# esp32-dev-board-v1_1.net
KiCad netlist of a schematic drawn in EasyEDA Pro
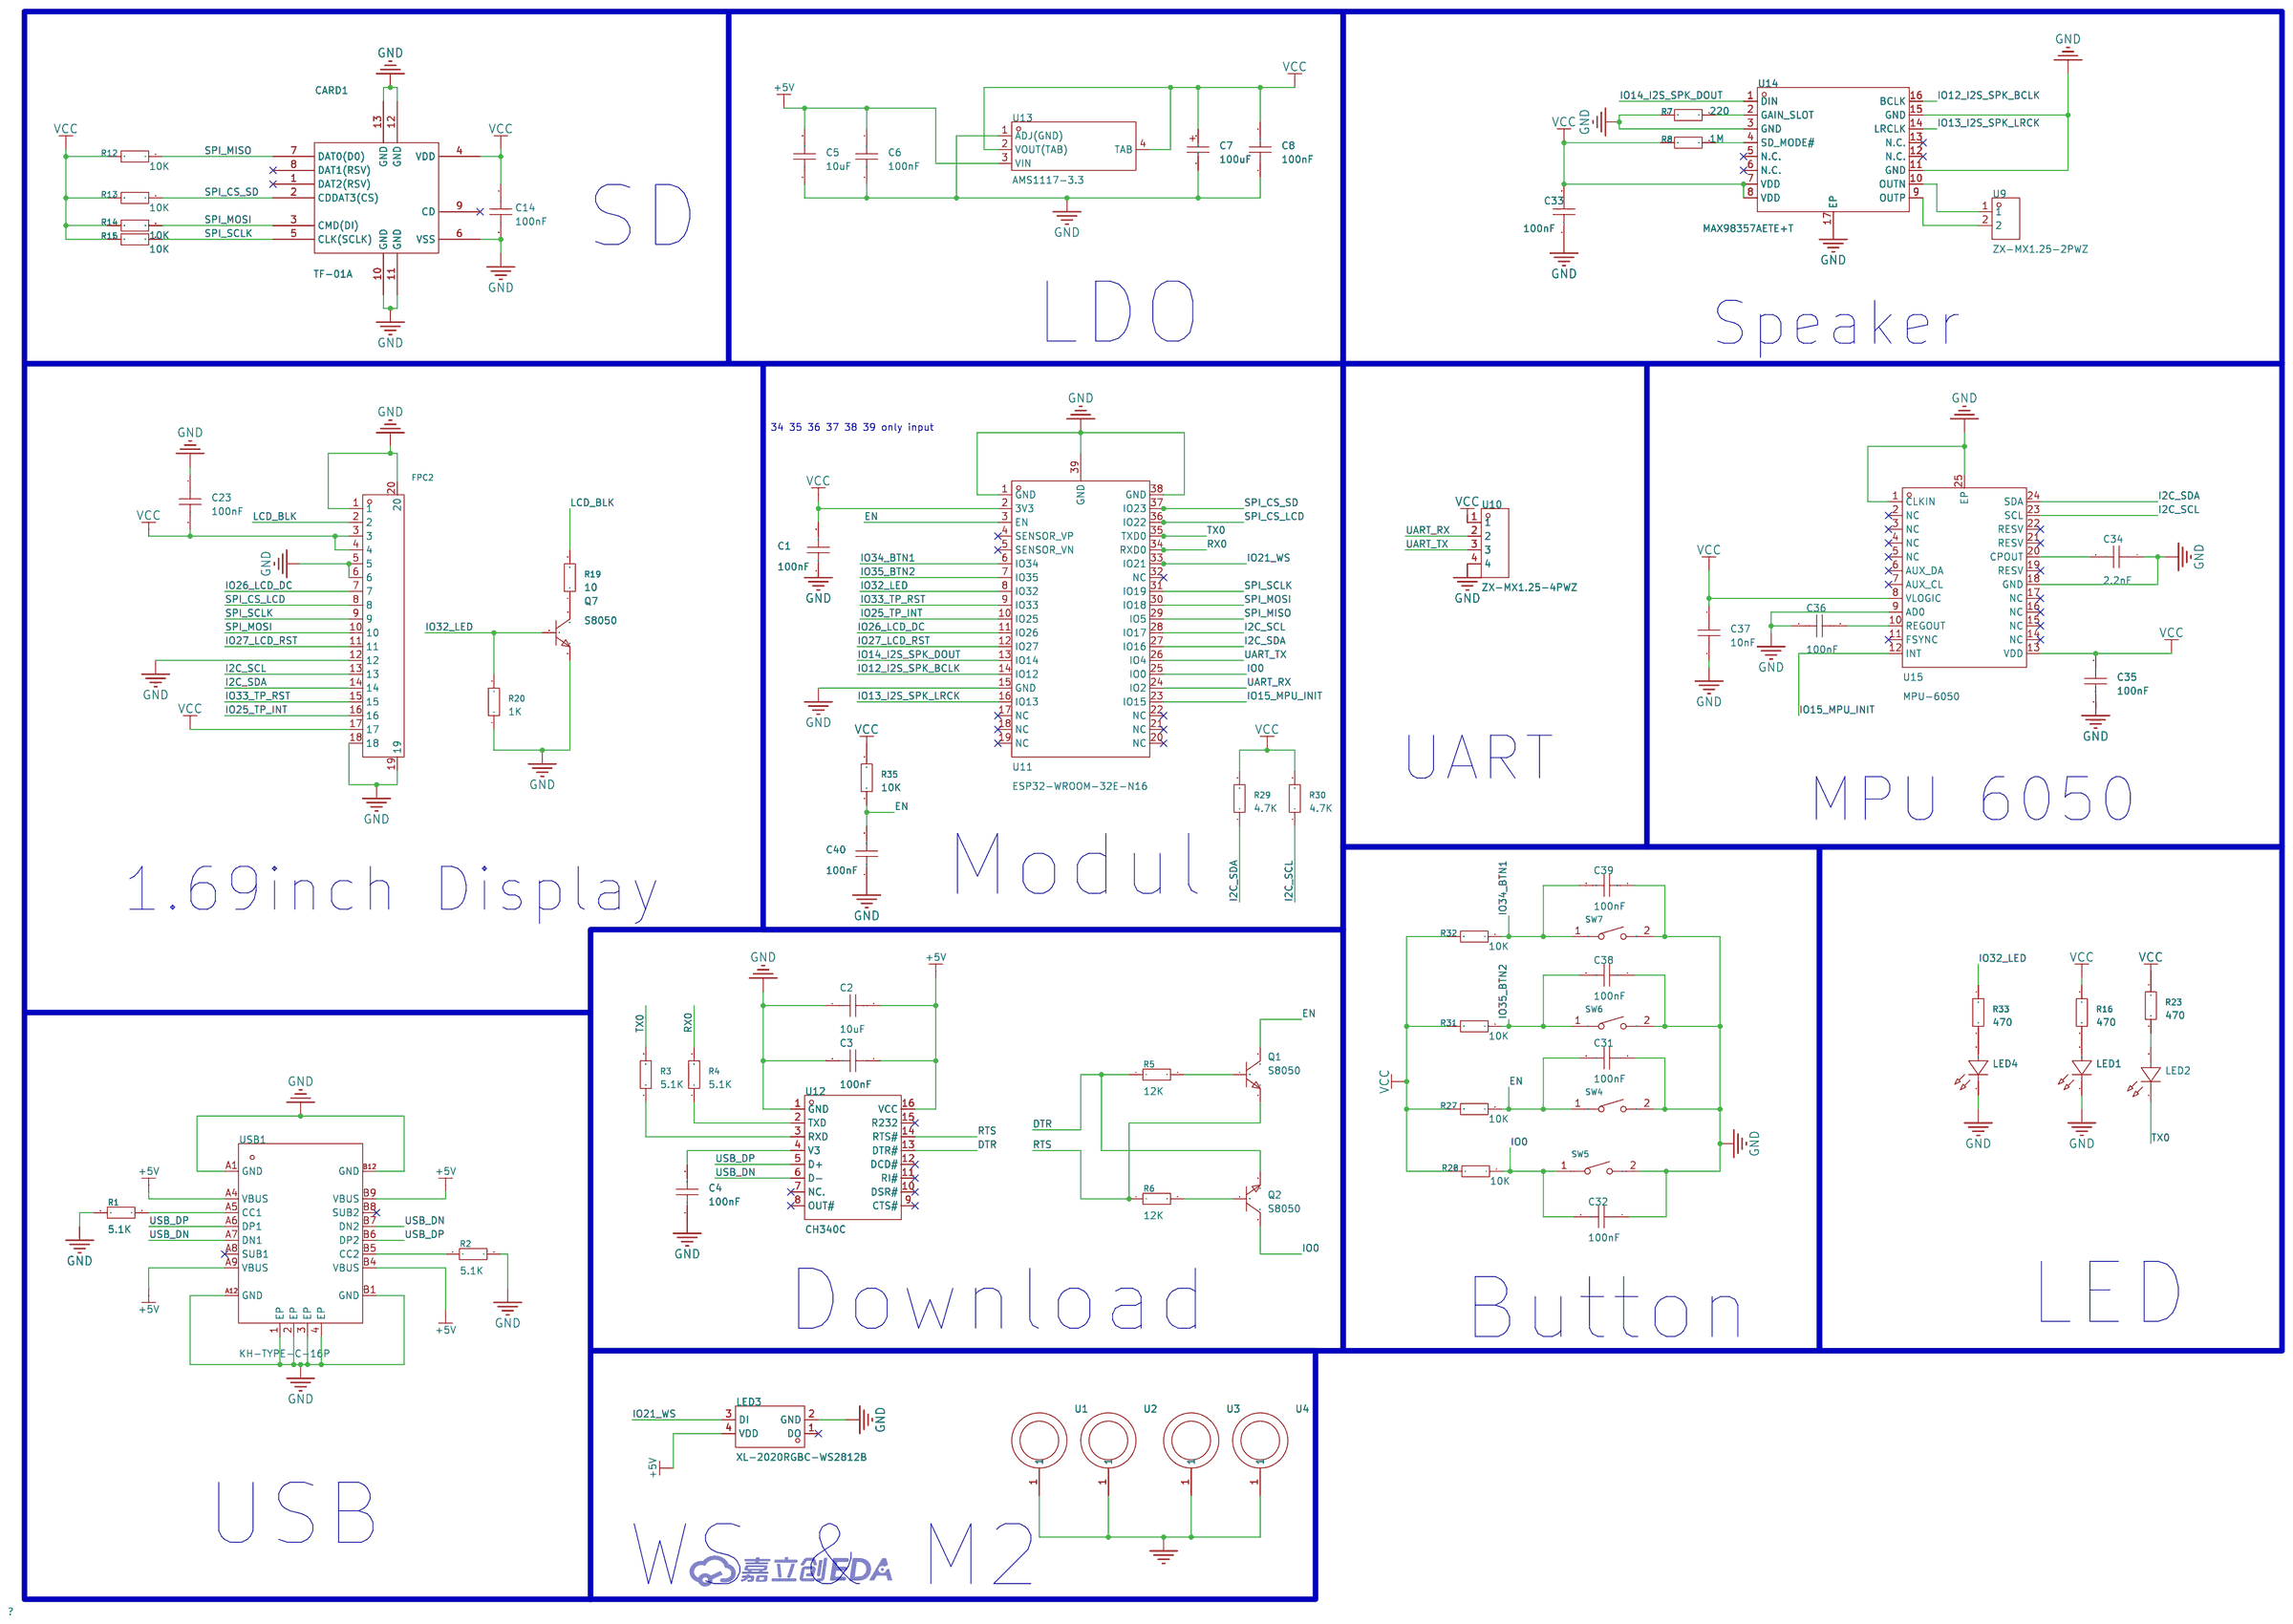
[diagram p0: schematic sheet]

(export (version "E")
  (design (tool "Eeschema 10.0.6"))
  (components
    (comp (ref "C1")
      (value "100nF")
      (footprint "easyedapro:C0402")
      (fields
        (field (name "Manufacturer Part") "CL05B104KO5NNNC")
        (field (name "Manufacturer") "SAMSUNG(三星)")
      )
      (libsource (lib "easyedapro") (part "CL05B104KO5NNNC"))
    )
    (comp (ref "C2")
      (value "10uF")
      (footprint "easyedapro:C0603")
      (fields
        (field (name "Manufacturer Part") "CGA0603X5R106K100JT")
        (field (name "Manufacturer") "HRE(芯声)")
      )
      (libsource (lib "easyedapro") (part "CGA0603X5R106K100JT"))
    )
    (comp (ref "C3")
      (value "100nF")
      (footprint "easyedapro:C0402")
      (fields
        (field (name "Manufacturer Part") "CL05B104KO5NNNC")
        (field (name "Manufacturer") "SAMSUNG(三星)")
      )
      (libsource (lib "easyedapro") (part "CL05B104KO5NNNC"))
    )
    (comp (ref "C4")
      (value "100nF")
      (footprint "easyedapro:C0402")
      (fields
        (field (name "Manufacturer Part") "CL05B104KO5NNNC")
        (field (name "Manufacturer") "SAMSUNG(三星)")
      )
      (libsource (lib "easyedapro") (part "CL05B104KO5NNNC"))
    )
    (comp (ref "C5")
      (value "10uF")
      (footprint "easyedapro:C0603")
      (fields
        (field (name "Manufacturer Part") "CGA0603X5R106K100JT")
        (field (name "Manufacturer") "HRE(芯声)")
      )
      (libsource (lib "easyedapro") (part "CGA0603X5R106K100JT"))
    )
    (comp (ref "C6")
      (value "100nF")
      (footprint "easyedapro:C0402")
      (fields
        (field (name "Manufacturer Part") "CL05B104KO5NNNC")
        (field (name "Manufacturer") "SAMSUNG(三星)")
      )
      (libsource (lib "easyedapro") (part "CL05B104KO5NNNC"))
    )
    (comp (ref "C7")
      (value "100uF")
      (footprint "easyedapro:CASE-B_3528")
      (fields (field (name "Manufacturer Part") "TAJB107K006RNJ") (field (name "Manufacturer") "Kyocera AVX"))
      (libsource (lib "easyedapro") (part "TAJB107K006RNJ"))
    )
    (comp (ref "C8")
      (value "100nF")
      (footprint "easyedapro:C0402")
      (fields
        (field (name "Manufacturer Part") "CL05B104KO5NNNC")
        (field (name "Manufacturer") "SAMSUNG(三星)")
      )
      (libsource (lib "easyedapro") (part "CL05B104KO5NNNC"))
    )
    (comp (ref "C14")
      (value "100nF")
      (footprint "easyedapro:C0402")
      (fields
        (field (name "Manufacturer Part") "CL05B104KO5NNNC")
        (field (name "Manufacturer") "SAMSUNG(三星)")
      )
      (libsource (lib "easyedapro") (part "CL05B104KO5NNNC"))
    )
    (comp (ref "C23")
      (value "100nF")
      (footprint "easyedapro:C0402")
      (fields
        (field (name "Manufacturer Part") "CL05B104KO5NNNC")
        (field (name "Manufacturer") "SAMSUNG(三星)")
      )
      (libsource (lib "easyedapro") (part "CL05B104KO5NNNC"))
    )
    (comp (ref "C31")
      (value "100nF")
      (footprint "easyedapro:C0402")
      (fields
        (field (name "Manufacturer Part") "CL05B104KO5NNNC")
        (field (name "Manufacturer") "SAMSUNG(三星)")
      )
      (libsource (lib "easyedapro") (part "CL05B104KO5NNNC"))
    )
    (comp (ref "C32")
      (value "100nF")
      (footprint "easyedapro:C0402")
      (fields
        (field (name "Manufacturer Part") "CL05B104KO5NNNC")
        (field (name "Manufacturer") "SAMSUNG(三星)")
      )
      (libsource (lib "easyedapro") (part "CL05B104KO5NNNC"))
    )
    (comp (ref "C33")
      (value "100nF")
      (footprint "easyedapro:C0402")
      (fields
        (field (name "Manufacturer Part") "CL05B104KO5NNNC")
        (field (name "Manufacturer") "SAMSUNG(三星)")
      )
      (libsource (lib "easyedapro") (part "CL05B104KO5NNNC"))
    )
    (comp (ref "C34")
      (value "2.2nF")
      (footprint "easyedapro:C0402")
      (fields
        (field (name "Manufacturer Part") "CL05B104KO5NNNC")
        (field (name "Manufacturer") "SAMSUNG(三星)")
      )
      (libsource (lib "easyedapro") (part "CL05B104KO5NNNC"))
    )
    (comp (ref "C35")
      (value "100nF")
      (footprint "easyedapro:C0402")
      (fields
        (field (name "Manufacturer Part") "CL05B104KO5NNNC")
        (field (name "Manufacturer") "SAMSUNG(三星)")
      )
      (libsource (lib "easyedapro") (part "CL05B104KO5NNNC"))
    )
    (comp (ref "C36")
      (value "100nF")
      (footprint "easyedapro:C0402")
      (fields
        (field (name "Manufacturer Part") "CL05B104KO5NNNC")
        (field (name "Manufacturer") "SAMSUNG(三星)")
      )
      (libsource (lib "easyedapro") (part "CL05B104KO5NNNC"))
    )
    (comp (ref "C37")
      (value "10nF")
      (footprint "easyedapro:C0402")
      (fields
        (field (name "Manufacturer Part") "CL05B104KO5NNNC")
        (field (name "Manufacturer") "SAMSUNG(三星)")
      )
      (libsource (lib "easyedapro") (part "CL05B104KO5NNNC"))
    )
    (comp (ref "C38")
      (value "100nF")
      (footprint "easyedapro:C0402")
      (fields
        (field (name "Manufacturer Part") "CL05B104KO5NNNC")
        (field (name "Manufacturer") "SAMSUNG(三星)")
      )
      (libsource (lib "easyedapro") (part "CL05B104KO5NNNC"))
    )
    (comp (ref "C39")
      (value "100nF")
      (footprint "easyedapro:C0402")
      (fields
        (field (name "Manufacturer Part") "CL05B104KO5NNNC")
        (field (name "Manufacturer") "SAMSUNG(三星)")
      )
      (libsource (lib "easyedapro") (part "CL05B104KO5NNNC"))
    )
    (comp (ref "C40")
      (value "100nF")
      (footprint "easyedapro:C0402")
      (fields
        (field (name "Manufacturer Part") "CL05B104KO5NNNC")
        (field (name "Manufacturer") "SAMSUNG(三星)")
      )
      (libsource (lib "easyedapro") (part "CL05B104KO5NNNC"))
    )
    (comp (ref "CARD1")
      (value "TF-01A")
      (footprint "easyedapro:TF-SMD_TF-01A")
      (fields (field (name "Manufacturer") "韩国韩荣"))
      (libsource (lib "easyedapro") (part "TF-01A"))
    )
    (comp (ref "FPC2")
      (value "FPC-05F-18PH20")
      (footprint "easyedapro:FPC-SMD_18P-P0.50_FPC-05F-18PH20")
      (fields (field (name "Manufacturer") "XUNPU(讯普)"))
      (libsource (lib "easyedapro") (part "FPC-05F-18PH20"))
    )
    (comp (ref "LED1")
      (value "XL-1608SURC-06")
      (footprint "easyedapro:LED0603-RD_RED")
      (fields (field (name "Manufacturer") "XINGLIGHT(成兴光)"))
      (libsource (lib "easyedapro") (part "XL-1608SURC-06"))
    )
    (comp (ref "LED2")
      (value "XL-1608SURC-06")
      (footprint "easyedapro:LED0603-RD_RED")
      (fields (field (name "Manufacturer") "XINGLIGHT(成兴光)"))
      (libsource (lib "easyedapro") (part "XL-1608SURC-06"))
    )
    (comp (ref "LED3")
      (value "XL-2020RGBC-WS2812B")
      (footprint "easyedapro:LED-SMD_4P-L2.0-W2.0-BR-1")
      (fields (field (name "Manufacturer") "XINGLIGHT(成兴光)"))
      (libsource (lib "easyedapro") (part "XL-2020RGBC-WS2812B"))
    )
    (comp (ref "LED4")
      (value "XL-1608SURC-06")
      (footprint "easyedapro:LED0603-RD_RED")
      (fields (field (name "Manufacturer") "XINGLIGHT(成兴光)"))
      (libsource (lib "easyedapro") (part "XL-1608SURC-06"))
    )
    (comp (ref "Q1")
      (value "S8050")
      (footprint "easyedapro:SOT-23-3_L2.9-W1.3-P1.90-LS2.3-BR")
      (fields (field (name "Manufacturer") "宏迦橙"))
      (libsource (lib "easyedapro") (part "S8050_C20069125"))
    )
    (comp (ref "Q2")
      (value "S8050")
      (footprint "easyedapro:SOT-23-3_L2.9-W1.3-P1.90-LS2.3-BR")
      (fields (field (name "Manufacturer") "宏迦橙"))
      (libsource (lib "easyedapro") (part "S8050_C20069125"))
    )
    (comp (ref "Q7")
      (value "S8050")
      (fields (field (name "Manufacturer") "宏迦橙"))
      (libsource (lib "easyedapro") (part "S8050_C20069125"))
    )
    (comp (ref "R1")
      (value "5.1K")
      (footprint "easyedapro:R0402")
      (fields
        (field (name "Manufacturer Part") "0402WGF4700TCE")
        (field (name "Manufacturer") "UNI-ROYAL(厚声)")
      )
      (libsource (lib "easyedapro") (part "0402WGF4700TCE"))
    )
    (comp (ref "R2")
      (value "5.1K")
      (footprint "easyedapro:R0402")
      (fields
        (field (name "Manufacturer Part") "0402WGF4700TCE")
        (field (name "Manufacturer") "UNI-ROYAL(厚声)")
      )
      (libsource (lib "easyedapro") (part "0402WGF4700TCE"))
    )
    (comp (ref "R3")
      (value "5.1K")
      (footprint "easyedapro:R0402")
      (fields
        (field (name "Manufacturer Part") "0402WGF4700TCE")
        (field (name "Manufacturer") "UNI-ROYAL(厚声)")
      )
      (libsource (lib "easyedapro") (part "0402WGF4700TCE"))
    )
    (comp (ref "R4")
      (value "5.1K")
      (footprint "easyedapro:R0402")
      (fields
        (field (name "Manufacturer Part") "0402WGF4700TCE")
        (field (name "Manufacturer") "UNI-ROYAL(厚声)")
      )
      (libsource (lib "easyedapro") (part "0402WGF4700TCE"))
    )
    (comp (ref "R5")
      (value "12K")
      (footprint "easyedapro:R0402")
      (fields
        (field (name "Manufacturer Part") "0402WGF4700TCE")
        (field (name "Manufacturer") "UNI-ROYAL(厚声)")
      )
      (libsource (lib "easyedapro") (part "0402WGF4700TCE"))
    )
    (comp (ref "R6")
      (value "12K")
      (footprint "easyedapro:R0402")
      (fields
        (field (name "Manufacturer Part") "0402WGF4700TCE")
        (field (name "Manufacturer") "UNI-ROYAL(厚声)")
      )
      (libsource (lib "easyedapro") (part "0402WGF4700TCE"))
    )
    (comp (ref "R7")
      (value "220")
      (footprint "easyedapro:R0402")
      (fields
        (field (name "Manufacturer Part") "0402WGF4700TCE")
        (field (name "Manufacturer") "UNI-ROYAL(厚声)")
      )
      (libsource (lib "easyedapro") (part "0402WGF4700TCE"))
    )
    (comp (ref "R8")
      (value "1M")
      (footprint "easyedapro:R0402")
      (fields
        (field (name "Manufacturer Part") "0402WGF4700TCE")
        (field (name "Manufacturer") "UNI-ROYAL(厚声)")
      )
      (libsource (lib "easyedapro") (part "0402WGF4700TCE"))
    )
    (comp (ref "R12")
      (value "10K")
      (footprint "easyedapro:R0402")
      (fields
        (field (name "Manufacturer Part") "0402WGF4700TCE")
        (field (name "Manufacturer") "UNI-ROYAL(厚声)")
      )
      (libsource (lib "easyedapro") (part "0402WGF4700TCE"))
    )
    (comp (ref "R13")
      (value "10K")
      (footprint "easyedapro:R0402")
      (fields
        (field (name "Manufacturer Part") "0402WGF4700TCE")
        (field (name "Manufacturer") "UNI-ROYAL(厚声)")
      )
      (libsource (lib "easyedapro") (part "0402WGF4700TCE"))
    )
    (comp (ref "R14")
      (value "10K")
      (footprint "easyedapro:R0402")
      (fields
        (field (name "Manufacturer Part") "0402WGF4700TCE")
        (field (name "Manufacturer") "UNI-ROYAL(厚声)")
      )
      (libsource (lib "easyedapro") (part "0402WGF4700TCE"))
    )
    (comp (ref "R15")
      (value "10K")
      (footprint "easyedapro:R0402")
      (fields
        (field (name "Manufacturer Part") "0402WGF4700TCE")
        (field (name "Manufacturer") "UNI-ROYAL(厚声)")
      )
      (libsource (lib "easyedapro") (part "0402WGF4700TCE"))
    )
    (comp (ref "R16")
      (value "470")
      (footprint "easyedapro:R0402")
      (fields
        (field (name "Manufacturer Part") "0402WGF4700TCE")
        (field (name "Manufacturer") "UNI-ROYAL(厚声)")
      )
      (libsource (lib "easyedapro") (part "0402WGF4700TCE"))
    )
    (comp (ref "R19")
      (value "10")
      (footprint "easyedapro:R0402")
      (fields
        (field (name "Manufacturer Part") "0402WGF4700TCE")
        (field (name "Manufacturer") "UNI-ROYAL(厚声)")
      )
      (libsource (lib "easyedapro") (part "0402WGF4700TCE"))
    )
    (comp (ref "R20")
      (value "1K")
      (footprint "easyedapro:R0402")
      (fields
        (field (name "Manufacturer Part") "0402WGF4700TCE")
        (field (name "Manufacturer") "UNI-ROYAL(厚声)")
      )
      (libsource (lib "easyedapro") (part "0402WGF4700TCE"))
    )
    (comp (ref "R23")
      (value "470")
      (footprint "easyedapro:R0402")
      (fields
        (field (name "Manufacturer Part") "0402WGF4700TCE")
        (field (name "Manufacturer") "UNI-ROYAL(厚声)")
      )
      (libsource (lib "easyedapro") (part "0402WGF4700TCE"))
    )
    (comp (ref "R27")
      (value "10K")
      (footprint "easyedapro:R0402")
      (fields
        (field (name "Manufacturer Part") "0402WGF4700TCE")
        (field (name "Manufacturer") "UNI-ROYAL(厚声)")
      )
      (libsource (lib "easyedapro") (part "0402WGF4700TCE"))
    )
    (comp (ref "R28")
      (value "10K")
      (footprint "easyedapro:R0402")
      (fields
        (field (name "Manufacturer Part") "0402WGF4700TCE")
        (field (name "Manufacturer") "UNI-ROYAL(厚声)")
      )
      (libsource (lib "easyedapro") (part "0402WGF4700TCE"))
    )
    (comp (ref "R29")
      (value "4.7K")
      (footprint "easyedapro:R0402")
      (fields
        (field (name "Manufacturer Part") "0402WGF4700TCE")
        (field (name "Manufacturer") "UNI-ROYAL(厚声)")
      )
      (libsource (lib "easyedapro") (part "0402WGF4700TCE"))
    )
    (comp (ref "R30")
      (value "4.7K")
      (footprint "easyedapro:R0402")
      (fields
        (field (name "Manufacturer Part") "0402WGF4700TCE")
        (field (name "Manufacturer") "UNI-ROYAL(厚声)")
      )
      (libsource (lib "easyedapro") (part "0402WGF4700TCE"))
    )
    (comp (ref "R31")
      (value "10K")
      (footprint "easyedapro:R0402")
      (fields
        (field (name "Manufacturer Part") "0402WGF4700TCE")
        (field (name "Manufacturer") "UNI-ROYAL(厚声)")
      )
      (libsource (lib "easyedapro") (part "0402WGF4700TCE"))
    )
    (comp (ref "R32")
      (value "10K")
      (footprint "easyedapro:R0402")
      (fields
        (field (name "Manufacturer Part") "0402WGF4700TCE")
        (field (name "Manufacturer") "UNI-ROYAL(厚声)")
      )
      (libsource (lib "easyedapro") (part "0402WGF4700TCE"))
    )
    (comp (ref "R33")
      (value "470")
      (footprint "easyedapro:R0402")
      (fields
        (field (name "Manufacturer Part") "0402WGF4700TCE")
        (field (name "Manufacturer") "UNI-ROYAL(厚声)")
      )
      (libsource (lib "easyedapro") (part "0402WGF4700TCE"))
    )
    (comp (ref "R35")
      (value "10K")
      (footprint "easyedapro:R0402")
      (fields
        (field (name "Manufacturer Part") "0402WGF4700TCE")
        (field (name "Manufacturer") "UNI-ROYAL(厚声)")
      )
      (libsource (lib "easyedapro") (part "0402WGF4700TCE"))
    )
    (comp (ref "SW4")
      (value "TS-1088-AR02016")
      (footprint "easyedapro:SW-SMD_L3.9-W3.0-P4.45")
      (fields (field (name "Manufacturer") "XUNPU(讯普)"))
      (libsource (lib "easyedapro") (part "TS-1088-AR02016"))
    )
    (comp (ref "SW5")
      (value "TS-1088-AR02016")
      (footprint "easyedapro:SW-SMD_L3.9-W3.0-P4.45")
      (fields (field (name "Manufacturer") "XUNPU(讯普)"))
      (libsource (lib "easyedapro") (part "TS-1088-AR02016"))
    )
    (comp (ref "SW6")
      (value "TS-1088-AR02016")
      (footprint "easyedapro:SW-SMD_L3.9-W3.0-P4.45")
      (fields (field (name "Manufacturer") "XUNPU(讯普)"))
      (libsource (lib "easyedapro") (part "TS-1088-AR02016"))
    )
    (comp (ref "SW7")
      (value "TS-1088-AR02016")
      (footprint "easyedapro:SW-SMD_L3.9-W3.0-P4.45")
      (fields (field (name "Manufacturer") "XUNPU(讯普)"))
      (libsource (lib "easyedapro") (part "TS-1088-AR02016"))
    )
    (comp (ref "U1") (value "~") (footprint "easyedapro:M2") (libsource (lib "easyedapro") (part "M2")))
    (comp (ref "U2") (value "~") (footprint "easyedapro:M2") (libsource (lib "easyedapro") (part "M2")))
    (comp (ref "U3") (value "~") (footprint "easyedapro:M2") (libsource (lib "easyedapro") (part "M2")))
    (comp (ref "U4") (value "~") (footprint "easyedapro:M2") (libsource (lib "easyedapro") (part "M2")))
    (comp (ref "U9")
      (value "ZX-MX1.25-2PWZ")
      (footprint "easyedapro:CONN-TH_2P-P1.25_ZX-MX1.25-2PWZ")
      (fields (field (name "Manufacturer") "Megastar(兆星)"))
      (libsource (lib "easyedapro") (part "ZX-MX1.25-2PWZ"))
    )
    (comp (ref "U10")
      (value "ZX-MX1.25-4PWZ")
      (footprint "easyedapro:CONN-TH_4P-P1.25_ZX-MX1.25-4PWZ")
      (fields (field (name "Manufacturer") "Megastar(兆星)"))
      (libsource (lib "easyedapro") (part "ZX-MX1.25-4PWZ"))
    )
    (comp (ref "U11")
      (value "ESP32-WROOM-32E-N16")
      (footprint "easyedapro:WIFI-SMD_ESP32-WROOM-32E")
      (fields (field (name "Manufacturer") "ESPRESSIF(乐鑫)"))
      (libsource (lib "easyedapro") (part "ESP32-WROOM-32E(16MB)"))
    )
    (comp (ref "U12")
      (value "CH340C")
      (footprint "easyedapro:SOP-16_L10.0-W3.9-P1.27-LS6.0-BL")
      (fields (field (name "Manufacturer") "WCH(南京沁恒)"))
      (libsource (lib "easyedapro") (part "CH340C"))
    )
    (comp (ref "U13")
      (value "AMS1117-3.3")
      (footprint "easyedapro:SOT-223-4_L6.5-W3.5-P2.30-LS7.0-BR")
      (fields (field (name "Manufacturer") "UMW(友台半导体)"))
      (libsource (lib "easyedapro") (part "AMS1117-3.3_C347222"))
    )
    (comp (ref "U14")
      (value "MAX98357AETE+T")
      (footprint "easyedapro:TQFN-16_L3.0-W3.0-P0.50-BL-EP1.5")
      (fields (field (name "Manufacturer") "ADI(亚德诺)/MAXIM(美信)"))
      (libsource (lib "easyedapro") (part "MAX98357AETE+T"))
    )
    (comp (ref "U15")
      (value "MPU-6050")
      (footprint "easyedapro:QFN-24_L4.0-W4.0-P0.50-BL-EP2.7")
      (description "Sensor Type:加速度计陀螺仪 Operating Temperature:-40°C~+85°C Operating Temperature:-40°C~+85°C")
      (fields (field (name "Manufacturer") "TDK InvenSense(应美盛)"))
      (libsource (lib "easyedapro") (part "MPU-6050_C24112"))
    )
    (comp (ref "USB1")
      (value "KH-TYPE-C-16P")
      (footprint "easyedapro:USB-C-SMD_KH-TYPE-C-16P")
      (fields (field (name "Manufacturer") "kinghelm(金航标)"))
      (libsource (lib "easyedapro") (part "KH-TYPE-C-16P"))
    )
  )
  (nets
    (net (code "1") (name "+5V") (class "Default")
      (node (ref "C2") (pin "2") (pinfunction "2_2") (pintype "unspecified"))
      (node (ref "C3") (pin "1") (pinfunction "1_1") (pintype "unspecified"))
      (node (ref "C5") (pin "2") (pinfunction "2_2") (pintype "unspecified"))
      (node (ref "C6") (pin "1") (pinfunction "1_1") (pintype "unspecified"))
      (node (ref "LED3") (pin "4") (pinfunction "VDD_4") (pintype "unspecified"))
      (node (ref "U12") (pin "16") (pinfunction "VCC_16") (pintype "unspecified"))
      (node (ref "U13") (pin "3") (pinfunction "VIN_3") (pintype "unspecified"))
      (node (ref "USB1") (pin "A4") (pinfunction "VBUS_A4") (pintype "unspecified"))
      (node (ref "USB1") (pin "A9") (pinfunction "VBUS_A9") (pintype "unspecified"))
      (node (ref "USB1") (pin "B4") (pinfunction "VBUS_B4") (pintype "unspecified"))
      (node (ref "USB1") (pin "B9") (pinfunction "VBUS_B9") (pintype "unspecified"))
    )
    (net (code "2") (name "/DTR") (class "Default")
      (node (ref "Q2") (pin "2") (pinfunction "E_2") (pintype "input"))
      (node (ref "R5") (pin "1") (pinfunction "1_1") (pintype "input"))
      (node (ref "U12") (pin "13") (pinfunction "DTR#_13") (pintype "unspecified"))
    )
    (net (code "3") (name "/EN") (class "Default")
      (node (ref "C31") (pin "2") (pinfunction "2_2") (pintype "unspecified"))
      (node (ref "C40") (pin "2") (pinfunction "2_2") (pintype "unspecified"))
      (node (ref "Q1") (pin "3") (pinfunction "C_3") (pintype "input"))
      (node (ref "R27") (pin "1") (pinfunction "1_1") (pintype "input"))
      (node (ref "R35") (pin "1") (pinfunction "1_1") (pintype "input"))
      (node (ref "SW4") (pin "1") (pinfunction "1_1") (pintype "input"))
      (node (ref "U11") (pin "3") (pinfunction "EN_3") (pintype "unspecified"))
    )
    (net (code "4") (name "/I2C_SCL") (class "Default")
      (node (ref "FPC2") (pin "13") (pinfunction "13_13") (pintype "input"))
      (node (ref "R30") (pin "1") (pinfunction "1_1") (pintype "input"))
      (node (ref "U11") (pin "28") (pinfunction "IO17_28") (pintype "unspecified"))
      (node (ref "U15") (pin "23") (pinfunction "SCL_23") (pintype "unspecified"))
    )
    (net (code "5") (name "/I2C_SDA") (class "Default")
      (node (ref "FPC2") (pin "14") (pinfunction "14_14") (pintype "input"))
      (node (ref "R29") (pin "1") (pinfunction "1_1") (pintype "input"))
      (node (ref "U11") (pin "27") (pinfunction "IO16_27") (pintype "unspecified"))
      (node (ref "U15") (pin "24") (pinfunction "SDA_24") (pintype "unspecified"))
    )
    (net (code "6") (name "/IO0") (class "Default")
      (node (ref "C32") (pin "2") (pinfunction "2_2") (pintype "unspecified"))
      (node (ref "Q2") (pin "3") (pinfunction "C_3") (pintype "input"))
      (node (ref "R28") (pin "1") (pinfunction "1_1") (pintype "input"))
      (node (ref "SW5") (pin "1") (pinfunction "1_1") (pintype "input"))
      (node (ref "U11") (pin "25") (pinfunction "IO0_25") (pintype "unspecified"))
    )
    (net (code "7") (name "/IO12_I2S_SPK_BCLK") (class "Default")
      (node (ref "U11") (pin "14") (pinfunction "IO12_14") (pintype "unspecified"))
      (node (ref "U14") (pin "16") (pinfunction "BCLK_16") (pintype "unspecified"))
    )
    (net (code "8") (name "/IO13_I2S_SPK_LRCK") (class "Default")
      (node (ref "U11") (pin "16") (pinfunction "IO13_16") (pintype "unspecified"))
      (node (ref "U14") (pin "14") (pinfunction "LRCLK_14") (pintype "unspecified"))
    )
    (net (code "9") (name "/IO14_I2S_SPK_DOUT") (class "Default")
      (node (ref "U11") (pin "13") (pinfunction "IO14_13") (pintype "unspecified"))
      (node (ref "U14") (pin "1") (pinfunction "DIN_1") (pintype "unspecified"))
    )
    (net (code "10") (name "/IO15_MPU_INIT") (class "Default")
      (node (ref "U11") (pin "23") (pinfunction "IO15_23") (pintype "unspecified"))
      (node (ref "U15") (pin "12") (pinfunction "INT_12") (pintype "unspecified"))
    )
    (net (code "11") (name "/IO21_WS") (class "Default")
      (node (ref "LED3") (pin "3") (pinfunction "DI_3") (pintype "unspecified"))
      (node (ref "U11") (pin "33") (pinfunction "IO21_33") (pintype "unspecified"))
    )
    (net (code "12") (name "/IO25_TP_INT") (class "Default")
      (node (ref "FPC2") (pin "16") (pinfunction "16_16") (pintype "input"))
      (node (ref "U11") (pin "10") (pinfunction "IO25_10") (pintype "unspecified"))
    )
    (net (code "13") (name "/IO26_LCD_DC") (class "Default")
      (node (ref "FPC2") (pin "7") (pinfunction "7_7") (pintype "input"))
      (node (ref "U11") (pin "11") (pinfunction "IO26_11") (pintype "unspecified"))
    )
    (net (code "14") (name "/IO27_LCD_RST") (class "Default")
      (node (ref "FPC2") (pin "11") (pinfunction "11_11") (pintype "input"))
      (node (ref "U11") (pin "12") (pinfunction "IO27_12") (pintype "unspecified"))
    )
    (net (code "15") (name "/IO32_LED") (class "Default")
      (node (ref "Q7") (pin "1") (pinfunction "B_1") (pintype "input"))
      (node (ref "R20") (pin "2") (pinfunction "2_2") (pintype "input"))
      (node (ref "R33") (pin "1") (pinfunction "1_1") (pintype "input"))
      (node (ref "U11") (pin "8") (pinfunction "IO32_8") (pintype "unspecified"))
    )
    (net (code "16") (name "/IO33_TP_RST") (class "Default")
      (node (ref "FPC2") (pin "15") (pinfunction "15_15") (pintype "input"))
      (node (ref "U11") (pin "9") (pinfunction "IO33_9") (pintype "unspecified"))
    )
    (net (code "17") (name "/IO34_BTN1") (class "Default")
      (node (ref "C39") (pin "2") (pinfunction "2_2") (pintype "unspecified"))
      (node (ref "R32") (pin "1") (pinfunction "1_1") (pintype "input"))
      (node (ref "SW7") (pin "1") (pinfunction "1_1") (pintype "input"))
      (node (ref "U11") (pin "6") (pinfunction "IO34_6") (pintype "unspecified"))
    )
    (net (code "18") (name "/IO35_BTN2") (class "Default")
      (node (ref "C38") (pin "2") (pinfunction "2_2") (pintype "unspecified"))
      (node (ref "R31") (pin "1") (pinfunction "1_1") (pintype "input"))
      (node (ref "SW6") (pin "1") (pinfunction "1_1") (pintype "input"))
      (node (ref "U11") (pin "7") (pinfunction "IO35_7") (pintype "unspecified"))
    )
    (net (code "19") (name "/LCD_BLK") (class "Default")
      (node (ref "FPC2") (pin "2") (pinfunction "2_2") (pintype "input"))
      (node (ref "R19") (pin "2") (pinfunction "2_2") (pintype "input"))
    )
    (net (code "20") (name "/RTS") (class "Default")
      (node (ref "Q1") (pin "2") (pinfunction "E_2") (pintype "input"))
      (node (ref "R6") (pin "1") (pinfunction "1_1") (pintype "input"))
      (node (ref "U12") (pin "14") (pinfunction "RTS#_14") (pintype "unspecified"))
    )
    (net (code "21") (name "/RX0") (class "Default")
      (node (ref "R4") (pin "2") (pinfunction "2_2") (pintype "input"))
      (node (ref "U11") (pin "34") (pinfunction "RXD0_34") (pintype "unspecified"))
    )
    (net (code "22") (name "/SPI_CS_LCD") (class "Default")
      (node (ref "FPC2") (pin "8") (pinfunction "8_8") (pintype "input"))
      (node (ref "U11") (pin "36") (pinfunction "IO22_36") (pintype "unspecified"))
    )
    (net (code "23") (name "/SPI_CS_SD") (class "Default")
      (node (ref "CARD1") (pin "2") (pinfunction "CDDAT3(CS)_2") (pintype "bidirectional"))
      (node (ref "R13") (pin "1") (pinfunction "1_1") (pintype "input"))
      (node (ref "U11") (pin "37") (pinfunction "IO23_37") (pintype "unspecified"))
    )
    (net (code "24") (name "/SPI_MISO") (class "Default")
      (node (ref "CARD1") (pin "7") (pinfunction "DAT0(D0)_7") (pintype "bidirectional"))
      (node (ref "R12") (pin "1") (pinfunction "1_1") (pintype "input"))
      (node (ref "U11") (pin "29") (pinfunction "IO5_29") (pintype "unspecified"))
    )
    (net (code "25") (name "/SPI_MOSI") (class "Default")
      (node (ref "CARD1") (pin "3") (pinfunction "CMD(DI)_3") (pintype "input"))
      (node (ref "FPC2") (pin "10") (pinfunction "10_10") (pintype "input"))
      (node (ref "R14") (pin "1") (pinfunction "1_1") (pintype "input"))
      (node (ref "U11") (pin "30") (pinfunction "IO18_30") (pintype "unspecified"))
    )
    (net (code "26") (name "/SPI_SCLK") (class "Default")
      (node (ref "CARD1") (pin "5") (pinfunction "CLK(SCLK)_5") (pintype "input"))
      (node (ref "FPC2") (pin "9") (pinfunction "9_9") (pintype "input"))
      (node (ref "R15") (pin "1") (pinfunction "1_1") (pintype "input"))
      (node (ref "U11") (pin "31") (pinfunction "IO19_31") (pintype "unspecified"))
    )
    (net (code "27") (name "/TX0") (class "Default")
      (node (ref "LED2") (pin "1") (pinfunction "K_1") (pintype "unspecified"))
      (node (ref "R3") (pin "2") (pinfunction "2_2") (pintype "input"))
      (node (ref "U11") (pin "35") (pinfunction "TXD0_35") (pintype "unspecified"))
    )
    (net (code "28") (name "/UART_RX") (class "Default")
      (node (ref "U10") (pin "2") (pinfunction "2_2") (pintype "unspecified"))
      (node (ref "U11") (pin "24") (pinfunction "IO2_24") (pintype "unspecified"))
    )
    (net (code "29") (name "/UART_TX") (class "Default")
      (node (ref "U10") (pin "3") (pinfunction "3_3") (pintype "unspecified"))
      (node (ref "U11") (pin "26") (pinfunction "IO4_26") (pintype "unspecified"))
    )
    (net (code "30") (name "/USB_DN") (class "Default")
      (node (ref "U12") (pin "6") (pinfunction "D-_6") (pintype "unspecified"))
      (node (ref "USB1") (pin "A7") (pinfunction "DN1_A7") (pintype "unspecified"))
      (node (ref "USB1") (pin "B7") (pinfunction "DN2_B7") (pintype "unspecified"))
    )
    (net (code "31") (name "/USB_DP") (class "Default")
      (node (ref "U12") (pin "5") (pinfunction "D+_5") (pintype "unspecified"))
      (node (ref "USB1") (pin "A6") (pinfunction "DP1_A6") (pintype "unspecified"))
      (node (ref "USB1") (pin "B6") (pinfunction "DP2_B6") (pintype "unspecified"))
    )
    (net (code "32") (name "GND") (class "Default")
      (node (ref "C1") (pin "1") (pinfunction "1_1") (pintype "unspecified"))
      (node (ref "C14") (pin "2") (pinfunction "2_2") (pintype "unspecified"))
      (node (ref "C2") (pin "1") (pinfunction "1_1") (pintype "unspecified"))
      (node (ref "C23") (pin "1") (pinfunction "1_1") (pintype "unspecified"))
      (node (ref "C3") (pin "2") (pinfunction "2_2") (pintype "unspecified"))
      (node (ref "C31") (pin "1") (pinfunction "1_1") (pintype "unspecified"))
      (node (ref "C32") (pin "1") (pinfunction "1_1") (pintype "unspecified"))
      (node (ref "C33") (pin "1") (pinfunction "1_1") (pintype "unspecified"))
      (node (ref "C34") (pin "1") (pinfunction "1_1") (pintype "unspecified"))
      (node (ref "C35") (pin "2") (pinfunction "2_2") (pintype "unspecified"))
      (node (ref "C36") (pin "1") (pinfunction "1_1") (pintype "unspecified"))
      (node (ref "C37") (pin "2") (pinfunction "2_2") (pintype "unspecified"))
      (node (ref "C38") (pin "1") (pinfunction "1_1") (pintype "unspecified"))
      (node (ref "C39") (pin "1") (pinfunction "1_1") (pintype "unspecified"))
      (node (ref "C4") (pin "1") (pinfunction "1_1") (pintype "unspecified"))
      (node (ref "C40") (pin "1") (pinfunction "1_1") (pintype "unspecified"))
      (node (ref "C5") (pin "1") (pinfunction "1_1") (pintype "unspecified"))
      (node (ref "C6") (pin "2") (pinfunction "2_2") (pintype "unspecified"))
      (node (ref "C7") (pin "2") (pinfunction "2_2") (pintype "input"))
      (node (ref "C8") (pin "1") (pinfunction "1_1") (pintype "unspecified"))
      (node (ref "CARD1") (pin "10") (pinfunction "GND_10") (pintype "input"))
      (node (ref "CARD1") (pin "11") (pinfunction "GND_11") (pintype "input"))
      (node (ref "CARD1") (pin "12") (pinfunction "GND_12") (pintype "input"))
      (node (ref "CARD1") (pin "13") (pinfunction "GND_13") (pintype "input"))
      (node (ref "CARD1") (pin "6") (pinfunction "VSS_6") (pintype "input"))
      (node (ref "FPC2") (pin "1") (pinfunction "1_1") (pintype "input"))
      (node (ref "FPC2") (pin "12") (pinfunction "12_12") (pintype "input"))
      (node (ref "FPC2") (pin "18") (pinfunction "18_18") (pintype "input"))
      (node (ref "FPC2") (pin "19") (pinfunction "19_19") (pintype "input"))
      (node (ref "FPC2") (pin "20") (pinfunction "20_20") (pintype "input"))
      (node (ref "FPC2") (pin "5") (pinfunction "5_5") (pintype "input"))
      (node (ref "FPC2") (pin "6") (pinfunction "6_6") (pintype "input"))
      (node (ref "LED1") (pin "1") (pinfunction "K_1") (pintype "unspecified"))
      (node (ref "LED3") (pin "2") (pinfunction "GND_2") (pintype "unspecified"))
      (node (ref "LED4") (pin "1") (pinfunction "K_1") (pintype "unspecified"))
      (node (ref "Q7") (pin "2") (pinfunction "E_2") (pintype "input"))
      (node (ref "R1") (pin "1") (pinfunction "1_1") (pintype "input"))
      (node (ref "R2") (pin "2") (pinfunction "2_2") (pintype "input"))
      (node (ref "R20") (pin "1") (pinfunction "1_1") (pintype "input"))
      (node (ref "R7") (pin "2") (pinfunction "2_2") (pintype "input"))
      (node (ref "SW4") (pin "2") (pinfunction "2_2") (pintype "input"))
      (node (ref "SW5") (pin "2") (pinfunction "2_2") (pintype "input"))
      (node (ref "SW6") (pin "2") (pinfunction "2_2") (pintype "input"))
      (node (ref "SW7") (pin "2") (pinfunction "2_2") (pintype "input"))
      (node (ref "U1") (pin "1") (pinfunction "1_1") (pintype "input"))
      (node (ref "U10") (pin "4") (pinfunction "4_4") (pintype "unspecified"))
      (node (ref "U11") (pin "1") (pinfunction "GND_1") (pintype "unspecified"))
      (node (ref "U11") (pin "15") (pinfunction "GND_15") (pintype "unspecified"))
      (node (ref "U11") (pin "38") (pinfunction "GND_38") (pintype "unspecified"))
      (node (ref "U11") (pin "39") (pinfunction "GND_39") (pintype "unspecified"))
      (node (ref "U12") (pin "1") (pinfunction "GND_1") (pintype "unspecified"))
      (node (ref "U13") (pin "1") (pinfunction "ADJ(GND)_1") (pintype "unspecified"))
      (node (ref "U14") (pin "11") (pinfunction "GND_11") (pintype "unspecified"))
      (node (ref "U14") (pin "15") (pinfunction "GND_15") (pintype "unspecified"))
      (node (ref "U14") (pin "17") (pinfunction "EP_17") (pintype "unspecified"))
      (node (ref "U14") (pin "3") (pinfunction "GND_3") (pintype "unspecified"))
      (node (ref "U15") (pin "1") (pinfunction "CLKIN_1") (pintype "unspecified"))
      (node (ref "U15") (pin "18") (pinfunction "GND_18") (pintype "unspecified"))
      (node (ref "U15") (pin "25") (pinfunction "EP_25") (pintype "unspecified"))
      (node (ref "U15") (pin "9") (pinfunction "AD0_9") (pintype "unspecified"))
      (node (ref "U2") (pin "1") (pinfunction "1_1") (pintype "input"))
      (node (ref "U3") (pin "1") (pinfunction "1_1") (pintype "input"))
      (node (ref "U4") (pin "1") (pinfunction "1_1") (pintype "input"))
      (node (ref "USB1") (pin "1") (pinfunction "EP_1") (pintype "unspecified"))
      (node (ref "USB1") (pin "2") (pinfunction "EP_2") (pintype "unspecified"))
      (node (ref "USB1") (pin "3") (pinfunction "EP_3") (pintype "unspecified"))
      (node (ref "USB1") (pin "4") (pinfunction "EP_4") (pintype "unspecified"))
      (node (ref "USB1") (pin "A1") (pinfunction "GND_A1") (pintype "unspecified"))
      (node (ref "USB1") (pin "A12") (pinfunction "GND_A12") (pintype "unspecified"))
      (node (ref "USB1") (pin "B1") (pinfunction "GND_B1") (pintype "unspecified"))
      (node (ref "USB1") (pin "B12") (pinfunction "GND_B12") (pintype "unspecified"))
    )
    (net (code "33") (name "Net-(LED1-A)") (class "Default")
      (node (ref "LED1") (pin "2") (pinfunction "A_2") (pintype "unspecified"))
      (node (ref "R16") (pin "2") (pinfunction "2_2") (pintype "input"))
    )
    (net (code "34") (name "Net-(LED2-A)") (class "Default")
      (node (ref "LED2") (pin "2") (pinfunction "A_2") (pintype "unspecified"))
      (node (ref "R23") (pin "2") (pinfunction "2_2") (pintype "input"))
    )
    (net (code "35") (name "Net-(LED4-A)") (class "Default")
      (node (ref "LED4") (pin "2") (pinfunction "A_2") (pintype "unspecified"))
      (node (ref "R33") (pin "2") (pinfunction "2_2") (pintype "input"))
    )
    (net (code "36") (name "Net-(Q1-B)") (class "Default")
      (node (ref "Q1") (pin "1") (pinfunction "B_1") (pintype "input"))
      (node (ref "R5") (pin "2") (pinfunction "2_2") (pintype "input"))
    )
    (net (code "37") (name "Net-(Q2-B)") (class "Default")
      (node (ref "Q2") (pin "1") (pinfunction "B_1") (pintype "input"))
      (node (ref "R6") (pin "2") (pinfunction "2_2") (pintype "input"))
    )
    (net (code "38") (name "Net-(Q7-C)") (class "Default")
      (node (ref "Q7") (pin "3") (pinfunction "C_3") (pintype "input"))
      (node (ref "R19") (pin "1") (pinfunction "1_1") (pintype "input"))
    )
    (net (code "39") (name "Net-(U12-RXD)") (class "Default")
      (node (ref "R3") (pin "1") (pinfunction "1_1") (pintype "input"))
      (node (ref "U12") (pin "3") (pinfunction "RXD_3") (pintype "unspecified"))
    )
    (net (code "40") (name "Net-(U12-TXD)") (class "Default")
      (node (ref "R4") (pin "1") (pinfunction "1_1") (pintype "input"))
      (node (ref "U12") (pin "2") (pinfunction "TXD_2") (pintype "unspecified"))
    )
    (net (code "41") (name "Net-(U12-V3)") (class "Default")
      (node (ref "C4") (pin "2") (pinfunction "2_2") (pintype "unspecified"))
      (node (ref "U12") (pin "4") (pinfunction "V3_4") (pintype "unspecified"))
    )
    (net (code "42") (name "Net-(U14-GAIN_SLOT)") (class "Default")
      (node (ref "R7") (pin "1") (pinfunction "1_1") (pintype "input"))
      (node (ref "U14") (pin "2") (pinfunction "GAIN_SLOT_2") (pintype "unspecified"))
    )
    (net (code "43") (name "Net-(U14-OUTN)") (class "Default")
      (node (ref "U14") (pin "10") (pinfunction "OUTN_10") (pintype "unspecified"))
      (node (ref "U9") (pin "1") (pinfunction "1_1") (pintype "unspecified"))
    )
    (net (code "44") (name "Net-(U14-OUTP)") (class "Default")
      (node (ref "U14") (pin "9") (pinfunction "OUTP_9") (pintype "unspecified"))
      (node (ref "U9") (pin "2") (pinfunction "2_2") (pintype "unspecified"))
    )
    (net (code "45") (name "Net-(U14-SD_MODE#)") (class "Default")
      (node (ref "R8") (pin "1") (pinfunction "1_1") (pintype "input"))
      (node (ref "U14") (pin "4") (pinfunction "SD_MODE#_4") (pintype "unspecified"))
    )
    (net (code "46") (name "Net-(U15-CPOUT)") (class "Default")
      (node (ref "C34") (pin "2") (pinfunction "2_2") (pintype "unspecified"))
      (node (ref "U15") (pin "20") (pinfunction "CPOUT_20") (pintype "unspecified"))
    )
    (net (code "47") (name "Net-(U15-REGOUT)") (class "Default")
      (node (ref "C36") (pin "2") (pinfunction "2_2") (pintype "unspecified"))
      (node (ref "U15") (pin "10") (pinfunction "REGOUT_10") (pintype "unspecified"))
    )
    (net (code "48") (name "Net-(USB1-CC1)") (class "Default")
      (node (ref "R1") (pin "2") (pinfunction "2_2") (pintype "input"))
      (node (ref "USB1") (pin "A5") (pinfunction "CC1_A5") (pintype "unspecified"))
    )
    (net (code "49") (name "Net-(USB1-CC2)") (class "Default")
      (node (ref "R2") (pin "1") (pinfunction "1_1") (pintype "input"))
      (node (ref "USB1") (pin "B5") (pinfunction "CC2_B5") (pintype "unspecified"))
    )
    (net (code "50") (name "VCC") (class "Default")
      (node (ref "C1") (pin "2") (pinfunction "2_2") (pintype "unspecified"))
      (node (ref "C14") (pin "1") (pinfunction "1_1") (pintype "unspecified"))
      (node (ref "C23") (pin "2") (pinfunction "2_2") (pintype "unspecified"))
      (node (ref "C33") (pin "2") (pinfunction "2_2") (pintype "unspecified"))
      (node (ref "C35") (pin "1") (pinfunction "1_1") (pintype "unspecified"))
      (node (ref "C37") (pin "1") (pinfunction "1_1") (pintype "unspecified"))
      (node (ref "C7") (pin "1") (pinfunction "1_1") (pintype "input"))
      (node (ref "C8") (pin "2") (pinfunction "2_2") (pintype "unspecified"))
      (node (ref "CARD1") (pin "4") (pinfunction "VDD_4") (pintype "input"))
      (node (ref "FPC2") (pin "17") (pinfunction "17_17") (pintype "input"))
      (node (ref "FPC2") (pin "3") (pinfunction "3_3") (pintype "input"))
      (node (ref "FPC2") (pin "4") (pinfunction "4_4") (pintype "input"))
      (node (ref "R12") (pin "2") (pinfunction "2_2") (pintype "input"))
      (node (ref "R13") (pin "2") (pinfunction "2_2") (pintype "input"))
      (node (ref "R14") (pin "2") (pinfunction "2_2") (pintype "input"))
      (node (ref "R15") (pin "2") (pinfunction "2_2") (pintype "input"))
      (node (ref "R16") (pin "1") (pinfunction "1_1") (pintype "input"))
      (node (ref "R23") (pin "1") (pinfunction "1_1") (pintype "input"))
      (node (ref "R27") (pin "2") (pinfunction "2_2") (pintype "input"))
      (node (ref "R28") (pin "2") (pinfunction "2_2") (pintype "input"))
      (node (ref "R29") (pin "2") (pinfunction "2_2") (pintype "input"))
      (node (ref "R30") (pin "2") (pinfunction "2_2") (pintype "input"))
      (node (ref "R31") (pin "2") (pinfunction "2_2") (pintype "input"))
      (node (ref "R32") (pin "2") (pinfunction "2_2") (pintype "input"))
      (node (ref "R35") (pin "2") (pinfunction "2_2") (pintype "input"))
      (node (ref "R8") (pin "2") (pinfunction "2_2") (pintype "input"))
      (node (ref "U10") (pin "1") (pinfunction "1_1") (pintype "unspecified"))
      (node (ref "U11") (pin "2") (pinfunction "3V3_2") (pintype "unspecified"))
      (node (ref "U13") (pin "2") (pinfunction "VOUT(TAB)_2") (pintype "unspecified"))
      (node (ref "U13") (pin "4") (pinfunction "TAB_4") (pintype "unspecified"))
      (node (ref "U14") (pin "7") (pinfunction "VDD_7") (pintype "unspecified"))
      (node (ref "U14") (pin "8") (pinfunction "VDD_8") (pintype "unspecified"))
      (node (ref "U15") (pin "13") (pinfunction "VDD_13") (pintype "unspecified"))
      (node (ref "U15") (pin "8") (pinfunction "VLOGIC_8") (pintype "unspecified"))
    )
    (net (code "51") (name "unconnected-(CARD1-CD-Pad9)") (class "Default")
      (node (ref "CARD1") (pin "9") (pinfunction "CD_9") (pintype "input+no_connect"))
    )
    (net (code "52") (name "unconnected-(CARD1-DAT1(RSV)-Pad8)") (class "Default")
      (node (ref "CARD1") (pin "8") (pinfunction "DAT1(RSV)_8") (pintype "bidirectional+no_connect"))
    )
    (net (code "53") (name "unconnected-(CARD1-DAT2(RSV)-Pad1)") (class "Default")
      (node (ref "CARD1") (pin "1") (pinfunction "DAT2(RSV)_1") (pintype "bidirectional+no_connect"))
    )
    (net (code "54") (name "unconnected-(LED3-DO-Pad1)") (class "Default")
      (node (ref "LED3") (pin "1") (pinfunction "DO_1") (pintype "unspecified+no_connect"))
    )
    (net (code "55") (name "unconnected-(U11-NC-Pad17)") (class "Default")
      (node (ref "U11") (pin "17") (pinfunction "NC_17") (pintype "unspecified+no_connect"))
    )
    (net (code "56") (name "unconnected-(U11-NC-Pad18)") (class "Default")
      (node (ref "U11") (pin "18") (pinfunction "NC_18") (pintype "unspecified+no_connect"))
    )
    (net (code "57") (name "unconnected-(U11-NC-Pad19)") (class "Default")
      (node (ref "U11") (pin "19") (pinfunction "NC_19") (pintype "unspecified+no_connect"))
    )
    (net (code "58") (name "unconnected-(U11-NC-Pad20)") (class "Default")
      (node (ref "U11") (pin "20") (pinfunction "NC_20") (pintype "unspecified+no_connect"))
    )
    (net (code "59") (name "unconnected-(U11-NC-Pad21)") (class "Default")
      (node (ref "U11") (pin "21") (pinfunction "NC_21") (pintype "unspecified+no_connect"))
    )
    (net (code "60") (name "unconnected-(U11-NC-Pad22)") (class "Default")
      (node (ref "U11") (pin "22") (pinfunction "NC_22") (pintype "unspecified+no_connect"))
    )
    (net (code "61") (name "unconnected-(U11-NC-Pad32)") (class "Default")
      (node (ref "U11") (pin "32") (pinfunction "NC_32") (pintype "unspecified+no_connect"))
    )
    (net (code "62") (name "unconnected-(U11-SENSOR_VN-Pad5)") (class "Default")
      (node (ref "U11") (pin "5") (pinfunction "SENSOR_VN_5") (pintype "unspecified+no_connect"))
    )
    (net (code "63") (name "unconnected-(U11-SENSOR_VP-Pad4)") (class "Default")
      (node (ref "U11") (pin "4") (pinfunction "SENSOR_VP_4") (pintype "unspecified+no_connect"))
    )
    (net (code "64") (name "unconnected-(U12-CTS#-Pad9)") (class "Default")
      (node (ref "U12") (pin "9") (pinfunction "CTS#_9") (pintype "unspecified+no_connect"))
    )
    (net (code "65") (name "unconnected-(U12-DCD#-Pad12)") (class "Default")
      (node (ref "U12") (pin "12") (pinfunction "DCD#_12") (pintype "unspecified+no_connect"))
    )
    (net (code "66") (name "unconnected-(U12-DSR#-Pad10)") (class "Default")
      (node (ref "U12") (pin "10") (pinfunction "DSR#_10") (pintype "unspecified+no_connect"))
    )
    (net (code "67") (name "unconnected-(U12-NC.-Pad7)") (class "Default")
      (node (ref "U12") (pin "7") (pinfunction "NC._7") (pintype "unspecified+no_connect"))
    )
    (net (code "68") (name "unconnected-(U12-OUT#-Pad8)") (class "Default")
      (node (ref "U12") (pin "8") (pinfunction "OUT#_8") (pintype "unspecified+no_connect"))
    )
    (net (code "69") (name "unconnected-(U12-R232-Pad15)") (class "Default")
      (node (ref "U12") (pin "15") (pinfunction "R232_15") (pintype "unspecified+no_connect"))
    )
    (net (code "70") (name "unconnected-(U12-RI#-Pad11)") (class "Default")
      (node (ref "U12") (pin "11") (pinfunction "RI#_11") (pintype "unspecified+no_connect"))
    )
    (net (code "71") (name "unconnected-(U14-N.C.-Pad5)") (class "Default")
      (node (ref "U14") (pin "5") (pinfunction "N.C._5") (pintype "unspecified+no_connect"))
    )
    (net (code "72") (name "unconnected-(U14-N.C.-Pad6)") (class "Default")
      (node (ref "U14") (pin "6") (pinfunction "N.C._6") (pintype "unspecified+no_connect"))
    )
    (net (code "73") (name "unconnected-(U14-N.C.-Pad12)") (class "Default")
      (node (ref "U14") (pin "12") (pinfunction "N.C._12") (pintype "unspecified+no_connect"))
    )
    (net (code "74") (name "unconnected-(U14-N.C.-Pad13)") (class "Default")
      (node (ref "U14") (pin "13") (pinfunction "N.C._13") (pintype "unspecified+no_connect"))
    )
    (net (code "75") (name "unconnected-(U15-AUX_CL-Pad7)") (class "Default")
      (node (ref "U15") (pin "7") (pinfunction "AUX_CL_7") (pintype "unspecified+no_connect"))
    )
    (net (code "76") (name "unconnected-(U15-AUX_DA-Pad6)") (class "Default")
      (node (ref "U15") (pin "6") (pinfunction "AUX_DA_6") (pintype "unspecified+no_connect"))
    )
    (net (code "77") (name "unconnected-(U15-FSYNC-Pad11)") (class "Default")
      (node (ref "U15") (pin "11") (pinfunction "FSYNC_11") (pintype "unspecified+no_connect"))
    )
    (net (code "78") (name "unconnected-(U15-NC-Pad2)") (class "Default")
      (node (ref "U15") (pin "2") (pinfunction "NC_2") (pintype "unspecified+no_connect"))
    )
    (net (code "79") (name "unconnected-(U15-NC-Pad3)") (class "Default")
      (node (ref "U15") (pin "3") (pinfunction "NC_3") (pintype "unspecified+no_connect"))
    )
    (net (code "80") (name "unconnected-(U15-NC-Pad4)") (class "Default")
      (node (ref "U15") (pin "4") (pinfunction "NC_4") (pintype "unspecified+no_connect"))
    )
    (net (code "81") (name "unconnected-(U15-NC-Pad5)") (class "Default")
      (node (ref "U15") (pin "5") (pinfunction "NC_5") (pintype "unspecified+no_connect"))
    )
    (net (code "82") (name "unconnected-(U15-NC-Pad14)") (class "Default")
      (node (ref "U15") (pin "14") (pinfunction "NC_14") (pintype "unspecified+no_connect"))
    )
    (net (code "83") (name "unconnected-(U15-NC-Pad15)") (class "Default")
      (node (ref "U15") (pin "15") (pinfunction "NC_15") (pintype "unspecified+no_connect"))
    )
    (net (code "84") (name "unconnected-(U15-NC-Pad16)") (class "Default")
      (node (ref "U15") (pin "16") (pinfunction "NC_16") (pintype "unspecified+no_connect"))
    )
    (net (code "85") (name "unconnected-(U15-NC-Pad17)") (class "Default")
      (node (ref "U15") (pin "17") (pinfunction "NC_17") (pintype "unspecified+no_connect"))
    )
    (net (code "86") (name "unconnected-(U15-RESV-Pad19)") (class "Default")
      (node (ref "U15") (pin "19") (pinfunction "RESV_19") (pintype "unspecified+no_connect"))
    )
    (net (code "87") (name "unconnected-(U15-RESV-Pad21)") (class "Default")
      (node (ref "U15") (pin "21") (pinfunction "RESV_21") (pintype "unspecified+no_connect"))
    )
    (net (code "88") (name "unconnected-(U15-RESV-Pad22)") (class "Default")
      (node (ref "U15") (pin "22") (pinfunction "RESV_22") (pintype "unspecified+no_connect"))
    )
    (net (code "89") (name "unconnected-(USB1-SUB1-PadA8)") (class "Default")
      (node (ref "USB1") (pin "A8") (pinfunction "SUB1_A8") (pintype "unspecified+no_connect"))
    )
    (net (code "90") (name "unconnected-(USB1-SUB2-PadB8)") (class "Default")
      (node (ref "USB1") (pin "B8") (pinfunction "SUB2_B8") (pintype "unspecified+no_connect"))
    )
  )
)
